# JTAG_Configuration.net
KiCad netlist of a schematic drawn in Altium Designer
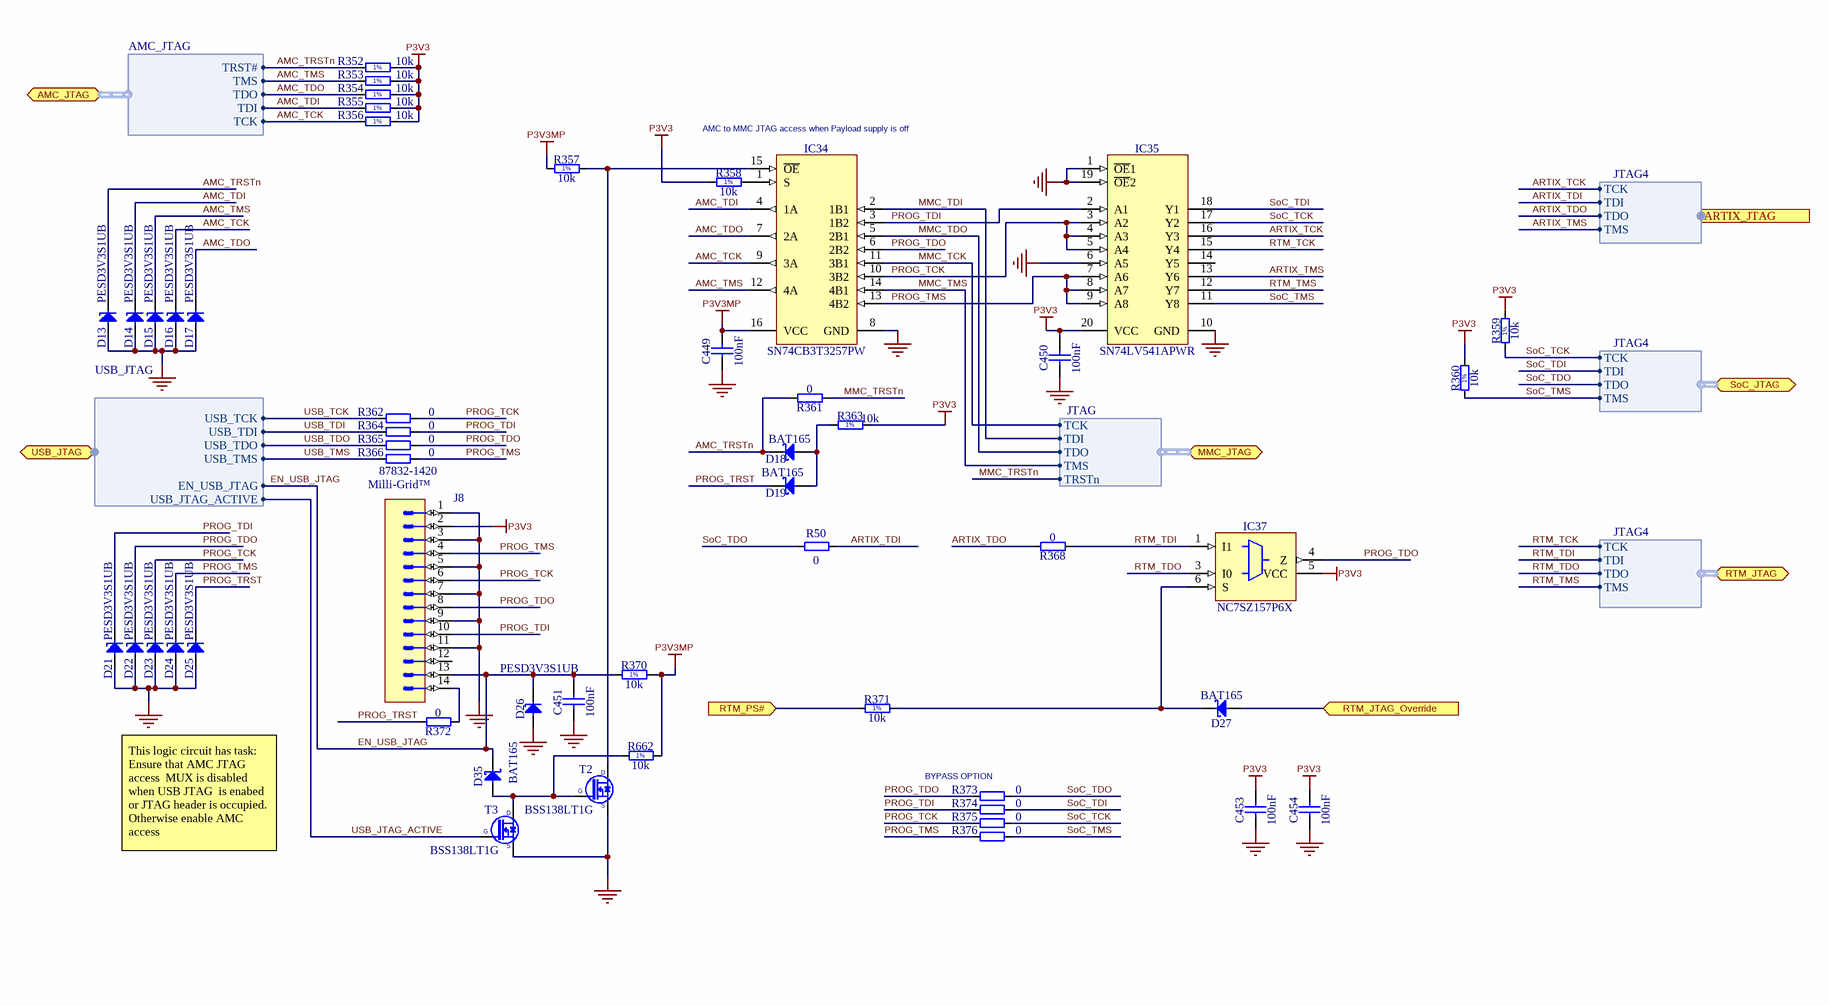
[diagram p0: JTAG_Configuration.SchDoc]

(export (version "E")
  (design (tool "Eeschema 10.0.6"))
  (components
    (comp (ref "C449")
      (value "100nF")
      (footprint "CAPC0603X33N")
      (description "Non-polarised capacitor")
      (fields
        (field (name "MANUFACTURER PART NUMBER") "CC0201_100NF_6.3V_10%_X5R")
        (field (name "MANUFACTURER") "GENERIC")
        (field (name "AUTHOR") "CERN DEM JLC")
      )
      (libsource (lib "Capacitors") (part "Capacitor - non polarized"))
    )
    (comp (ref "C450")
      (value "100nF")
      (footprint "CAPC0603X33N")
      (description "Non-polarised capacitor")
      (fields
        (field (name "MANUFACTURER PART NUMBER") "CC0201_100NF_6.3V_10%_X5R")
        (field (name "MANUFACTURER") "GENERIC")
        (field (name "AUTHOR") "CERN DEM JLC")
      )
      (libsource (lib "Capacitors") (part "Capacitor - non polarized"))
    )
    (comp (ref "C451")
      (value "100nF")
      (footprint "CAPC0603X33N")
      (description "Non-polarised capacitor")
      (fields
        (field (name "MANUFACTURER PART NUMBER") "CC0201_100NF_6.3V_10%_X5R")
        (field (name "MANUFACTURER") "GENERIC")
        (field (name "AUTHOR") "CERN DEM JLC")
      )
      (libsource (lib "Capacitors") (part "Capacitor - non polarized"))
    )
    (comp (ref "C453")
      (value "100nF")
      (footprint "CAPC0603X33N")
      (description "Non-polarised capacitor")
      (fields
        (field (name "MANUFACTURER PART NUMBER") "CC0201_100NF_6.3V_10%_X5R")
        (field (name "MANUFACTURER") "GENERIC")
        (field (name "AUTHOR") "CERN DEM JLC")
      )
      (libsource (lib "Capacitors") (part "Capacitor - non polarized"))
    )
    (comp (ref "C454")
      (value "100nF")
      (footprint "CAPC0603X33N")
      (description "Non-polarised capacitor")
      (fields
        (field (name "MANUFACTURER PART NUMBER") "CC0201_100NF_6.3V_10%_X5R")
        (field (name "MANUFACTURER") "GENERIC")
        (field (name "AUTHOR") "CERN DEM JLC")
      )
      (libsource (lib "Capacitors") (part "Capacitor - non polarized"))
    )
    (comp (ref "D13")
      (value "PESD3V3S1UB")
      (footprint "SODFL1608X65N")
      (description "ESD protection diode")
      (fields
        (field (name "MANUFACTURER") "NXP SEMICONDUCTORS")
        (field (name "VOLTAGE") "3V3")
        (field (name "AUTHOR") "CERN DEM JLC")
      )
      (libsource (lib "ICs And Semiconductors") (part "Diode ESD"))
    )
    (comp (ref "D14")
      (value "PESD3V3S1UB")
      (footprint "SODFL1608X65N")
      (description "ESD protection diode")
      (fields
        (field (name "MANUFACTURER") "NXP SEMICONDUCTORS")
        (field (name "VOLTAGE") "3V3")
        (field (name "AUTHOR") "CERN DEM JLC")
      )
      (libsource (lib "ICs And Semiconductors") (part "Diode ESD"))
    )
    (comp (ref "D15")
      (value "PESD3V3S1UB")
      (footprint "SODFL1608X65N")
      (description "ESD protection diode")
      (fields
        (field (name "MANUFACTURER") "NXP SEMICONDUCTORS")
        (field (name "VOLTAGE") "3V3")
        (field (name "AUTHOR") "CERN DEM JLC")
      )
      (libsource (lib "ICs And Semiconductors") (part "Diode ESD"))
    )
    (comp (ref "D16")
      (value "PESD3V3S1UB")
      (footprint "SODFL1608X65N")
      (description "ESD protection diode")
      (fields
        (field (name "MANUFACTURER") "NXP SEMICONDUCTORS")
        (field (name "VOLTAGE") "3V3")
        (field (name "AUTHOR") "CERN DEM JLC")
      )
      (libsource (lib "ICs And Semiconductors") (part "Diode ESD"))
    )
    (comp (ref "D17")
      (value "PESD3V3S1UB")
      (footprint "SODFL1608X65N")
      (description "ESD protection diode")
      (fields
        (field (name "MANUFACTURER") "NXP SEMICONDUCTORS")
        (field (name "VOLTAGE") "3V3")
        (field (name "AUTHOR") "CERN DEM JLC")
      )
      (libsource (lib "ICs And Semiconductors") (part "Diode ESD"))
    )
    (comp (ref "D18")
      (value "BAT165")
      (footprint "SOD2512X110N")
      (description "Schottky Diode")
      (fields
        (field (name "MANUFACTURER") "INFINEON")
        (field (name "VOLTAGE") "40V")
        (field (name "AUTHOR") "CERN DEM JLC")
      )
      (libsource (lib "ICs And Semiconductors") (part "Diode Schottky"))
    )
    (comp (ref "D19")
      (value "BAT165")
      (footprint "SOD2512X110N")
      (description "Schottky Diode")
      (fields
        (field (name "MANUFACTURER") "INFINEON")
        (field (name "VOLTAGE") "40V")
        (field (name "AUTHOR") "CERN DEM JLC")
      )
      (libsource (lib "ICs And Semiconductors") (part "Diode Schottky"))
    )
    (comp (ref "D21")
      (value "PESD3V3S1UB")
      (footprint "SODFL1608X65N")
      (description "ESD protection diode")
      (fields
        (field (name "MANUFACTURER") "NXP SEMICONDUCTORS")
        (field (name "VOLTAGE") "3V3")
        (field (name "AUTHOR") "CERN DEM JLC")
      )
      (libsource (lib "ICs And Semiconductors") (part "Diode ESD"))
    )
    (comp (ref "D22")
      (value "PESD3V3S1UB")
      (footprint "SODFL1608X65N")
      (description "ESD protection diode")
      (fields
        (field (name "MANUFACTURER") "NXP SEMICONDUCTORS")
        (field (name "VOLTAGE") "3V3")
        (field (name "AUTHOR") "CERN DEM JLC")
      )
      (libsource (lib "ICs And Semiconductors") (part "Diode ESD"))
    )
    (comp (ref "D23")
      (value "PESD3V3S1UB")
      (footprint "SODFL1608X65N")
      (description "ESD protection diode")
      (fields
        (field (name "MANUFACTURER") "NXP SEMICONDUCTORS")
        (field (name "VOLTAGE") "3V3")
        (field (name "AUTHOR") "CERN DEM JLC")
      )
      (libsource (lib "ICs And Semiconductors") (part "Diode ESD"))
    )
    (comp (ref "D24")
      (value "PESD3V3S1UB")
      (footprint "SODFL1608X65N")
      (description "ESD protection diode")
      (fields
        (field (name "MANUFACTURER") "NXP SEMICONDUCTORS")
        (field (name "VOLTAGE") "3V3")
        (field (name "AUTHOR") "CERN DEM JLC")
      )
      (libsource (lib "ICs And Semiconductors") (part "Diode ESD"))
    )
    (comp (ref "D25")
      (value "PESD3V3S1UB")
      (footprint "SODFL1608X65N")
      (description "ESD protection diode")
      (fields
        (field (name "MANUFACTURER") "NXP SEMICONDUCTORS")
        (field (name "VOLTAGE") "3V3")
        (field (name "AUTHOR") "CERN DEM JLC")
      )
      (libsource (lib "ICs And Semiconductors") (part "Diode ESD"))
    )
    (comp (ref "D26")
      (value "PESD3V3S1UB")
      (footprint "SODFL1608X65N")
      (description "ESD protection diode")
      (fields
        (field (name "MANUFACTURER") "NXP SEMICONDUCTORS")
        (field (name "VOLTAGE") "3V3")
        (field (name "AUTHOR") "CERN DEM JLC")
      )
      (libsource (lib "ICs And Semiconductors") (part "Diode ESD"))
    )
    (comp (ref "D27")
      (value "BAT165")
      (footprint "SOD2512X110N")
      (description "Schottky Diode")
      (fields
        (field (name "MANUFACTURER") "INFINEON")
        (field (name "VOLTAGE") "40V")
        (field (name "AUTHOR") "CERN DEM JLC")
      )
      (libsource (lib "ICs And Semiconductors") (part "Diode Schottky"))
    )
    (comp (ref "D35")
      (value "BAT165")
      (footprint "SOD2512X110N")
      (description "Schottky Diode")
      (fields
        (field (name "MANUFACTURER") "INFINEON")
        (field (name "VOLTAGE") "40V")
        (field (name "AUTHOR") "CERN DEM JLC")
      )
      (libsource (lib "ICs And Semiconductors") (part "Diode Schottky"))
    )
    (comp (ref "IC34")
      (value "SN74CB3T3257PW")
      (footprint "SOP65P640X120-16N")
      (description "4-BIT 1-OF-2 FET Multiplexer/Demultiplexer 2.5V/3.3V Low-Voltage Bus Switch 5V Tolerant Shifter")
      (fields (field (name "MANUFACTURER") "TEXAS INSTRUMENTS") (field (name "AUTHOR") "CERN DEM JLC"))
      (libsource (lib "ICs And Semiconductors") (part "743257"))
    )
    (comp (ref "IC35")
      (value "SN74LV541APWR")
      (footprint "SOP65P640X120-20N")
      (description "Octal Buffer/Line Driver with 3-State Outputs")
      (fields (field (name "MANUFACTURER") "TEXAS INSTRUMENTS") (field (name "AUTHOR") "CERN DEM JLC"))
      (libsource (lib "ICs And Semiconductors") (part "74541"))
    )
    (comp (ref "IC37")
      (value "NC7SZ157P6X")
      (footprint "SOT65P210X110-6N")
      (description "TinyLogic® UHS 2-Input Non-Inverting Multiplexer")
      (fields (field (name "MANUFACTURER") "FAIRCHILD SEMICONDUCTOR") (field (name "AUTHOR") "CERN DEM JLC"))
      (libsource (lib "ICs And Semiconductors") (part "NC7SZ157"))
    )
    (comp (ref "J8")
      (value "Milli-Grid™")
      (footprint "MOLEX_87832-1420")
      (description "Connector 14 Male")
      (fields
        (field (name "MANUFACTURER PART NUMBER") "87832-1420")
        (field (name "MANUFACTURER") "MOLEX")
        (field (name "PART NUMBER") "MOLEX_87832-1420")
        (field (name "AUTHOR") "CERN DEM JLC")
      )
      (libsource (lib "Connectors") (part "Connector 14 Male"))
    )
    (comp (ref "R50")
      (value "0")
      (footprint "RESC1005X40N")
      (description "Resistor")
      (fields
        (field (name "MANUFACTURER PART NUMBER") "R0402_0R_JUMPER")
        (field (name "MANUFACTURER") "GENERIC")
        (field (name "AUTHOR") "CERN DEM JLC")
      )
      (libsource (lib "Resistors") (part "Resistor"))
    )
    (comp (ref "R352")
      (value "10k")
      (footprint "RESC1005X40N")
      (description "Resistor - 1%")
      (fields
        (field (name "MANUFACTURER PART NUMBER") "R0402_10K_1%_0.0625W_100PPM")
        (field (name "MANUFACTURER") "GENERIC")
        (field (name "AUTHOR") "CERN DEM JLC")
      )
      (libsource (lib "Resistors") (part "Resistor - 1%"))
    )
    (comp (ref "R353")
      (value "10k")
      (footprint "RESC1005X40N")
      (description "Resistor - 1%")
      (fields
        (field (name "MANUFACTURER PART NUMBER") "R0402_10K_1%_0.0625W_100PPM")
        (field (name "MANUFACTURER") "GENERIC")
        (field (name "AUTHOR") "CERN DEM JLC")
      )
      (libsource (lib "Resistors") (part "Resistor - 1%"))
    )
    (comp (ref "R354")
      (value "10k")
      (footprint "RESC1005X40N")
      (description "Resistor - 1%")
      (fields
        (field (name "MANUFACTURER PART NUMBER") "R0402_10K_1%_0.0625W_100PPM")
        (field (name "MANUFACTURER") "GENERIC")
        (field (name "AUTHOR") "CERN DEM JLC")
      )
      (libsource (lib "Resistors") (part "Resistor - 1%"))
    )
    (comp (ref "R355")
      (value "10k")
      (footprint "RESC1005X40N")
      (description "Resistor - 1%")
      (fields
        (field (name "MANUFACTURER PART NUMBER") "R0402_10K_1%_0.0625W_100PPM")
        (field (name "MANUFACTURER") "GENERIC")
        (field (name "AUTHOR") "CERN DEM JLC")
      )
      (libsource (lib "Resistors") (part "Resistor - 1%"))
    )
    (comp (ref "R356")
      (value "10k")
      (footprint "RESC1005X40N")
      (description "Resistor - 1%")
      (fields
        (field (name "MANUFACTURER PART NUMBER") "R0402_10K_1%_0.0625W_100PPM")
        (field (name "MANUFACTURER") "GENERIC")
        (field (name "AUTHOR") "CERN DEM JLC")
      )
      (libsource (lib "Resistors") (part "Resistor - 1%"))
    )
    (comp (ref "R357")
      (value "10k")
      (footprint "RESC1005X40N")
      (description "Resistor - 1%")
      (fields
        (field (name "MANUFACTURER PART NUMBER") "R0402_10K_1%_0.0625W_100PPM")
        (field (name "MANUFACTURER") "GENERIC")
        (field (name "AUTHOR") "CERN DEM JLC")
      )
      (libsource (lib "Resistors") (part "Resistor - 1%"))
    )
    (comp (ref "R358")
      (value "10k")
      (footprint "RESC1005X40N")
      (description "Resistor - 1%")
      (fields
        (field (name "MANUFACTURER PART NUMBER") "R0402_10K_1%_0.0625W_100PPM")
        (field (name "MANUFACTURER") "GENERIC")
        (field (name "AUTHOR") "CERN DEM JLC")
      )
      (libsource (lib "Resistors") (part "Resistor - 1%"))
    )
    (comp (ref "R359")
      (value "10k")
      (footprint "RESC1005X40N")
      (description "Resistor - 1%")
      (fields
        (field (name "MANUFACTURER PART NUMBER") "R0402_10K_1%_0.0625W_100PPM")
        (field (name "MANUFACTURER") "GENERIC")
        (field (name "AUTHOR") "CERN DEM JLC")
      )
      (libsource (lib "Resistors") (part "Resistor - 1%"))
    )
    (comp (ref "R360")
      (value "10k")
      (footprint "RESC1005X40N")
      (description "Resistor - 1%")
      (fields
        (field (name "MANUFACTURER PART NUMBER") "R0402_10K_1%_0.0625W_100PPM")
        (field (name "MANUFACTURER") "GENERIC")
        (field (name "AUTHOR") "CERN DEM JLC")
      )
      (libsource (lib "Resistors") (part "Resistor - 1%"))
    )
    (comp (ref "R361")
      (value "0")
      (footprint "RESC1005X40N")
      (description "Resistor")
      (fields
        (field (name "MANUFACTURER PART NUMBER") "R0402_0R_JUMPER")
        (field (name "MANUFACTURER") "GENERIC")
        (field (name "AUTHOR") "CERN DEM JLC")
      )
      (libsource (lib "Resistors") (part "Resistor"))
    )
    (comp (ref "R362")
      (value "0")
      (footprint "RESC1005X40N")
      (description "Resistor")
      (fields
        (field (name "MANUFACTURER PART NUMBER") "R0402_0R_JUMPER")
        (field (name "MANUFACTURER") "GENERIC")
        (field (name "AUTHOR") "CERN DEM JLC")
      )
      (libsource (lib "Resistors") (part "Resistor"))
    )
    (comp (ref "R363")
      (value "10k")
      (footprint "RESC1005X40N")
      (description "Resistor - 1%")
      (fields
        (field (name "MANUFACTURER PART NUMBER") "R0402_10K_1%_0.0625W_100PPM")
        (field (name "MANUFACTURER") "GENERIC")
        (field (name "AUTHOR") "CERN DEM JLC")
      )
      (libsource (lib "Resistors") (part "Resistor - 1%"))
    )
    (comp (ref "R364")
      (value "0")
      (footprint "RESC1005X40N")
      (description "Resistor")
      (fields
        (field (name "MANUFACTURER PART NUMBER") "R0402_0R_JUMPER")
        (field (name "MANUFACTURER") "GENERIC")
        (field (name "AUTHOR") "CERN DEM JLC")
      )
      (libsource (lib "Resistors") (part "Resistor"))
    )
    (comp (ref "R365")
      (value "0")
      (footprint "RESC1005X40N")
      (description "Resistor")
      (fields
        (field (name "MANUFACTURER PART NUMBER") "R0402_0R_JUMPER")
        (field (name "MANUFACTURER") "GENERIC")
        (field (name "AUTHOR") "CERN DEM JLC")
      )
      (libsource (lib "Resistors") (part "Resistor"))
    )
    (comp (ref "R366")
      (value "0")
      (footprint "RESC1005X40N")
      (description "Resistor")
      (fields
        (field (name "MANUFACTURER PART NUMBER") "R0402_0R_JUMPER")
        (field (name "MANUFACTURER") "GENERIC")
        (field (name "AUTHOR") "CERN DEM JLC")
      )
      (libsource (lib "Resistors") (part "Resistor"))
    )
    (comp (ref "R368")
      (value "0")
      (footprint "RESC1005X40N")
      (description "Resistor")
      (fields
        (field (name "MANUFACTURER PART NUMBER") "R0402_0R_JUMPER")
        (field (name "MANUFACTURER") "GENERIC")
        (field (name "AUTHOR") "CERN DEM JLC")
      )
      (libsource (lib "Resistors") (part "Resistor"))
    )
    (comp (ref "R370")
      (value "10k")
      (footprint "RESC1005X40N")
      (description "Resistor - 1%")
      (fields
        (field (name "MANUFACTURER PART NUMBER") "R0402_10K_1%_0.0625W_100PPM")
        (field (name "MANUFACTURER") "GENERIC")
        (field (name "AUTHOR") "CERN DEM JLC")
      )
      (libsource (lib "Resistors") (part "Resistor - 1%"))
    )
    (comp (ref "R371")
      (value "10k")
      (footprint "RESC1005X40N")
      (description "Resistor - 1%")
      (fields
        (field (name "MANUFACTURER PART NUMBER") "R0402_10K_1%_0.0625W_100PPM")
        (field (name "MANUFACTURER") "GENERIC")
        (field (name "AUTHOR") "CERN DEM JLC")
      )
      (libsource (lib "Resistors") (part "Resistor - 1%"))
    )
    (comp (ref "R372")
      (value "0")
      (footprint "RESC1005X40N")
      (description "Resistor")
      (fields
        (field (name "MANUFACTURER PART NUMBER") "R0402_0R_JUMPER")
        (field (name "MANUFACTURER") "GENERIC")
        (field (name "AUTHOR") "CERN DEM JLC")
      )
      (libsource (lib "Resistors") (part "Resistor"))
    )
    (comp (ref "R373")
      (value "0")
      (footprint "RESC1005X40N")
      (description "Resistor")
      (fields
        (field (name "MANUFACTURER PART NUMBER") "R0402_0R_JUMPER")
        (field (name "MANUFACTURER") "GENERIC")
        (field (name "AUTHOR") "CERN DEM JLC")
      )
      (libsource (lib "Resistors") (part "Resistor"))
    )
    (comp (ref "R374")
      (value "0")
      (footprint "RESC1005X40N")
      (description "Resistor")
      (fields
        (field (name "MANUFACTURER PART NUMBER") "R0402_0R_JUMPER")
        (field (name "MANUFACTURER") "GENERIC")
        (field (name "AUTHOR") "CERN DEM JLC")
      )
      (libsource (lib "Resistors") (part "Resistor"))
    )
    (comp (ref "R375")
      (value "0")
      (footprint "RESC1005X40N")
      (description "Resistor")
      (fields
        (field (name "MANUFACTURER PART NUMBER") "R0402_0R_JUMPER")
        (field (name "MANUFACTURER") "GENERIC")
        (field (name "AUTHOR") "CERN DEM JLC")
      )
      (libsource (lib "Resistors") (part "Resistor"))
    )
    (comp (ref "R376")
      (value "0")
      (footprint "RESC1005X40N")
      (description "Resistor")
      (fields
        (field (name "MANUFACTURER PART NUMBER") "R0402_0R_JUMPER")
        (field (name "MANUFACTURER") "GENERIC")
        (field (name "AUTHOR") "CERN DEM JLC")
      )
      (libsource (lib "Resistors") (part "Resistor"))
    )
    (comp (ref "R662")
      (value "10k")
      (footprint "RESC1005X40N")
      (description "Resistor - 1%")
      (fields
        (field (name "MANUFACTURER PART NUMBER") "R0402_10K_1%_0.0625W_100PPM")
        (field (name "MANUFACTURER") "GENERIC")
        (field (name "AUTHOR") "CERN DEM JLC")
      )
      (libsource (lib "Resistors") (part "Resistor - 1%"))
    )
    (comp (ref "T2")
      (value "BSS138LT1G")
      (footprint "SOT95P240X110-3N")
      (description "N-CHANNEL MOSFET WITH DIODE")
      (fields (field (name "MANUFACTURER") "ON SEMICONDUCTOR") (field (name "AUTHOR") "CERN DEM JLC"))
      (libsource (lib "ICs And Semiconductors") (part "N-MOSFET-D 1G 2S 3D"))
    )
    (comp (ref "T3")
      (value "BSS138LT1G")
      (footprint "SOT95P240X110-3N")
      (description "N-CHANNEL MOSFET WITH DIODE")
      (fields (field (name "MANUFACTURER") "ON SEMICONDUCTOR") (field (name "AUTHOR") "CERN DEM JLC"))
      (libsource (lib "ICs And Semiconductors") (part "N-MOSFET-D 1G 2S 3D"))
    )
  )
  (nets
    (net (code "5") (name "/AMC_TCK") (class "Default")
      (node (ref "D16") (pin "1") (pinfunction "C_1") (pintype "passive"))
      (node (ref "IC34") (pin "9") (pinfunction "3A_9") (pintype "output"))
      (node (ref "R356") (pin "2") (pinfunction "2_2") (pintype "passive"))
    )
    (net (code "6") (name "/AMC_TDI") (class "Default")
      (node (ref "D14") (pin "1") (pinfunction "C_1") (pintype "passive"))
      (node (ref "IC34") (pin "4") (pinfunction "1A_4") (pintype "output"))
      (node (ref "R355") (pin "2") (pinfunction "2_2") (pintype "passive"))
    )
    (net (code "7") (name "/AMC_TDO") (class "Default")
      (node (ref "D17") (pin "1") (pinfunction "C_1") (pintype "passive"))
      (node (ref "IC34") (pin "7") (pinfunction "2A_7") (pintype "output"))
      (node (ref "R354") (pin "2") (pinfunction "2_2") (pintype "passive"))
    )
    (net (code "8") (name "/AMC_TMS") (class "Default")
      (node (ref "D15") (pin "1") (pinfunction "C_1") (pintype "passive"))
      (node (ref "IC34") (pin "12") (pinfunction "4A_12") (pintype "output"))
      (node (ref "R353") (pin "2") (pinfunction "2_2") (pintype "passive"))
    )
    (net (code "9") (name "/AMC_TRSTn") (class "Default")
      (node (ref "D13") (pin "1") (pinfunction "C_1") (pintype "passive"))
      (node (ref "D18") (pin "1") (pinfunction "C_1") (pintype "passive"))
      (node (ref "R352") (pin "2") (pinfunction "2_2") (pintype "passive"))
      (node (ref "R361") (pin "2") (pinfunction "2_2") (pintype "passive"))
    )
    (net (code "10") (name "/ARTIX_TCK") (class "Default")
      (node (ref "IC35") (pin "16") (pinfunction "Y3_16") (pintype "tri_state"))
    )
    (net (code "11") (name "/ARTIX_TDI") (class "Default")
      (node (ref "R50") (pin "1") (pinfunction "1_1") (pintype "passive"))
    )
    (net (code "12") (name "/ARTIX_TDO") (class "Default")
      (node (ref "R368") (pin "2") (pinfunction "2_2") (pintype "passive"))
    )
    (net (code "13") (name "/ARTIX_TMS") (class "Default")
      (node (ref "IC35") (pin "13") (pinfunction "Y6_13") (pintype "tri_state"))
    )
    (net (code "14") (name "/EN_USB_JTAG") (class "Default")
      (node (ref "C451") (pin "2") (pinfunction "2_2") (pintype "passive"))
      (node (ref "D26") (pin "1") (pinfunction "C_1") (pintype "passive"))
      (node (ref "D35") (pin "1") (pinfunction "C_1") (pintype "passive"))
      (node (ref "J8") (pin "13") (pinfunction "13_13") (pintype "bidirectional"))
      (node (ref "R370") (pin "1") (pinfunction "1_1") (pintype "passive"))
    )
    (net (code "15") (name "/MMC_TCK") (class "Default")
      (node (ref "IC34") (pin "11") (pinfunction "3B1_11") (pintype "input"))
    )
    (net (code "16") (name "/MMC_TDI") (class "Default")
      (node (ref "IC34") (pin "2") (pinfunction "1B1_2") (pintype "input"))
    )
    (net (code "17") (name "/MMC_TDO") (class "Default")
      (node (ref "IC34") (pin "5") (pinfunction "2B1_5") (pintype "input"))
    )
    (net (code "18") (name "/MMC_TMS") (class "Default")
      (node (ref "IC34") (pin "14") (pinfunction "4B1_14") (pintype "input"))
    )
    (net (code "19") (name "/MMC_TRSTn") (class "Default")
      (node (ref "R361") (pin "1") (pinfunction "1_1") (pintype "passive"))
    )
    (net (code "20") (name "/PROG_TCK") (class "Default")
      (node (ref "D23") (pin "1") (pinfunction "C_1") (pintype "passive"))
      (node (ref "IC34") (pin "10") (pinfunction "3B2_10") (pintype "input"))
      (node (ref "IC35") (pin "3") (pinfunction "A2_3") (pintype "input"))
      (node (ref "IC35") (pin "4") (pinfunction "A3_4") (pintype "input"))
      (node (ref "IC35") (pin "5") (pinfunction "A4_5") (pintype "input"))
      (node (ref "J8") (pin "6") (pinfunction "6_6") (pintype "bidirectional"))
      (node (ref "R362") (pin "1") (pinfunction "1_1") (pintype "passive"))
      (node (ref "R375") (pin "2") (pinfunction "2_2") (pintype "passive"))
    )
    (net (code "21") (name "/PROG_TDI") (class "Default")
      (node (ref "D21") (pin "1") (pinfunction "C_1") (pintype "passive"))
      (node (ref "IC34") (pin "3") (pinfunction "1B2_3") (pintype "input"))
      (node (ref "IC35") (pin "2") (pinfunction "A1_2") (pintype "input"))
      (node (ref "J8") (pin "10") (pinfunction "10_10") (pintype "bidirectional"))
      (node (ref "R364") (pin "1") (pinfunction "1_1") (pintype "passive"))
      (node (ref "R374") (pin "2") (pinfunction "2_2") (pintype "passive"))
    )
    (net (code "22") (name "/PROG_TDO") (class "Default")
      (node (ref "D22") (pin "1") (pinfunction "C_1") (pintype "passive"))
      (node (ref "IC34") (pin "6") (pinfunction "2B2_6") (pintype "input"))
      (node (ref "IC37") (pin "4") (pinfunction "Z_4") (pintype "output"))
      (node (ref "J8") (pin "8") (pinfunction "8_8") (pintype "bidirectional"))
      (node (ref "R365") (pin "1") (pinfunction "1_1") (pintype "passive"))
      (node (ref "R373") (pin "2") (pinfunction "2_2") (pintype "passive"))
    )
    (net (code "23") (name "/PROG_TMS") (class "Default")
      (node (ref "D24") (pin "1") (pinfunction "C_1") (pintype "passive"))
      (node (ref "IC34") (pin "13") (pinfunction "4B2_13") (pintype "input"))
      (node (ref "IC35") (pin "7") (pinfunction "A6_7") (pintype "input"))
      (node (ref "IC35") (pin "8") (pinfunction "A7_8") (pintype "input"))
      (node (ref "IC35") (pin "9") (pinfunction "A8_9") (pintype "input"))
      (node (ref "J8") (pin "4") (pinfunction "4_4") (pintype "bidirectional"))
      (node (ref "R366") (pin "1") (pinfunction "1_1") (pintype "passive"))
      (node (ref "R376") (pin "2") (pinfunction "2_2") (pintype "passive"))
    )
    (net (code "24") (name "/PROG_TRST") (class "Default")
      (node (ref "D19") (pin "1") (pinfunction "C_1") (pintype "passive"))
      (node (ref "D25") (pin "1") (pinfunction "C_1") (pintype "passive"))
      (node (ref "R372") (pin "2") (pinfunction "2_2") (pintype "passive"))
    )
    (net (code "25") (name "/RTM_JTAG_Override") (class "Default")
      (node (ref "D27") (pin "2") (pinfunction "A_2") (pintype "passive"))
    )
    (net (code "26") (name "/RTM_PS#") (class "Default")
      (node (ref "R371") (pin "2") (pinfunction "2_2") (pintype "passive"))
    )
    (net (code "27") (name "/RTM_TCK") (class "Default")
      (node (ref "IC35") (pin "15") (pinfunction "Y4_15") (pintype "tri_state"))
    )
    (net (code "28") (name "/RTM_TDI") (class "Default")
      (node (ref "IC37") (pin "1") (pinfunction "I1_1") (pintype "input"))
      (node (ref "R368") (pin "1") (pinfunction "1_1") (pintype "passive"))
    )
    (net (code "29") (name "/RTM_TDO") (class "Default")
      (node (ref "IC37") (pin "3") (pinfunction "I0_3") (pintype "input"))
    )
    (net (code "30") (name "/RTM_TMS") (class "Default")
      (node (ref "IC35") (pin "12") (pinfunction "Y7_12") (pintype "tri_state"))
    )
    (net (code "31") (name "/SoC_TCK") (class "Default")
      (node (ref "IC35") (pin "17") (pinfunction "Y2_17") (pintype "tri_state"))
      (node (ref "R359") (pin "1") (pinfunction "1_1") (pintype "passive"))
      (node (ref "R375") (pin "1") (pinfunction "1_1") (pintype "passive"))
    )
    (net (code "32") (name "/SoC_TDI") (class "Default")
      (node (ref "IC35") (pin "18") (pinfunction "Y1_18") (pintype "tri_state"))
      (node (ref "R374") (pin "1") (pinfunction "1_1") (pintype "passive"))
    )
    (net (code "33") (name "/SoC_TDO") (class "Default")
      (node (ref "R373") (pin "1") (pinfunction "1_1") (pintype "passive"))
      (node (ref "R50") (pin "2") (pinfunction "2_2") (pintype "passive"))
    )
    (net (code "34") (name "/SoC_TMS") (class "Default")
      (node (ref "IC35") (pin "11") (pinfunction "Y8_11") (pintype "tri_state"))
      (node (ref "R360") (pin "1") (pinfunction "1_1") (pintype "passive"))
      (node (ref "R376") (pin "1") (pinfunction "1_1") (pintype "passive"))
    )
    (net (code "35") (name "/USB_JTAG_ACTIVE") (class "Default")
      (node (ref "T3") (pin "1") (pinfunction "G_1") (pintype "passive"))
    )
    (net (code "36") (name "/USB_TCK") (class "Default")
      (node (ref "R362") (pin "2") (pinfunction "2_2") (pintype "passive"))
    )
    (net (code "37") (name "/USB_TDI") (class "Default")
      (node (ref "R364") (pin "2") (pinfunction "2_2") (pintype "passive"))
    )
    (net (code "38") (name "/USB_TDO") (class "Default")
      (node (ref "R365") (pin "2") (pinfunction "2_2") (pintype "passive"))
    )
    (net (code "39") (name "/USB_TMS") (class "Default")
      (node (ref "R366") (pin "2") (pinfunction "2_2") (pintype "passive"))
    )
    (net (code "44") (name "GND") (class "Default")
      (node (ref "C449") (pin "1") (pinfunction "1_1") (pintype "passive"))
      (node (ref "C450") (pin "1") (pinfunction "1_1") (pintype "passive"))
      (node (ref "C451") (pin "1") (pinfunction "1_1") (pintype "passive"))
      (node (ref "C453") (pin "1") (pinfunction "1_1") (pintype "passive"))
      (node (ref "C454") (pin "1") (pinfunction "1_1") (pintype "passive"))
      (node (ref "D13") (pin "2") (pinfunction "A_2") (pintype "passive"))
      (node (ref "D14") (pin "2") (pinfunction "A_2") (pintype "passive"))
      (node (ref "D15") (pin "2") (pinfunction "A_2") (pintype "passive"))
      (node (ref "D16") (pin "2") (pinfunction "A_2") (pintype "passive"))
      (node (ref "D17") (pin "2") (pinfunction "A_2") (pintype "passive"))
      (node (ref "D21") (pin "2") (pinfunction "A_2") (pintype "passive"))
      (node (ref "D22") (pin "2") (pinfunction "A_2") (pintype "passive"))
      (node (ref "D23") (pin "2") (pinfunction "A_2") (pintype "passive"))
      (node (ref "D24") (pin "2") (pinfunction "A_2") (pintype "passive"))
      (node (ref "D25") (pin "2") (pinfunction "A_2") (pintype "passive"))
      (node (ref "D26") (pin "2") (pinfunction "A_2") (pintype "passive"))
      (node (ref "IC34") (pin "8") (pinfunction "GND_8") (pintype "power_in"))
      (node (ref "IC35") (pin "1") (pinfunction "~{OE}1_1") (pintype "input"))
      (node (ref "IC35") (pin "10") (pinfunction "GND_10") (pintype "power_in"))
      (node (ref "IC35") (pin "19") (pinfunction "~{OE}2_19") (pintype "input"))
      (node (ref "IC35") (pin "6") (pinfunction "A5_6") (pintype "input"))
      (node (ref "IC37") (pin "2") (pinfunction "GND_2") (pintype "power_in"))
      (node (ref "J8") (pin "1") (pinfunction "1_1") (pintype "bidirectional"))
      (node (ref "J8") (pin "11") (pinfunction "11_11") (pintype "bidirectional"))
      (node (ref "J8") (pin "3") (pinfunction "3_3") (pintype "bidirectional"))
      (node (ref "J8") (pin "5") (pinfunction "5_5") (pintype "bidirectional"))
      (node (ref "J8") (pin "7") (pinfunction "7_7") (pintype "bidirectional"))
      (node (ref "J8") (pin "9") (pinfunction "9_9") (pintype "bidirectional"))
      (node (ref "T2") (pin "2") (pinfunction "S_2") (pintype "passive"))
      (node (ref "T3") (pin "2") (pinfunction "S_2") (pintype "passive"))
    )
    (net (code "45") (name "Net-(D18-A)") (class "Default")
      (node (ref "D18") (pin "2") (pinfunction "A_2") (pintype "passive"))
      (node (ref "D19") (pin "2") (pinfunction "A_2") (pintype "passive"))
      (node (ref "R363") (pin "2") (pinfunction "2_2") (pintype "passive"))
    )
    (net (code "46") (name "Net-(D27-C)") (class "Default")
      (node (ref "D27") (pin "1") (pinfunction "C_1") (pintype "passive"))
      (node (ref "IC37") (pin "6") (pinfunction "S_6") (pintype "input"))
      (node (ref "R371") (pin "1") (pinfunction "1_1") (pintype "passive"))
    )
    (net (code "47") (name "Net-(D35-A)") (class "Default")
      (node (ref "D35") (pin "2") (pinfunction "A_2") (pintype "passive"))
      (node (ref "R662") (pin "1") (pinfunction "1_1") (pintype "passive"))
      (node (ref "T2") (pin "1") (pinfunction "G_1") (pintype "passive"))
      (node (ref "T3") (pin "3") (pinfunction "D_3") (pintype "passive"))
    )
    (net (code "48") (name "Net-(IC34-S)") (class "Default")
      (node (ref "IC34") (pin "1") (pinfunction "S_1") (pintype "input"))
      (node (ref "R358") (pin "1") (pinfunction "1_1") (pintype "passive"))
    )
    (net (code "49") (name "Net-(IC34-~{OE})") (class "Default")
      (node (ref "IC34") (pin "15") (pinfunction "~{OE}_15") (pintype "input"))
      (node (ref "R357") (pin "1") (pinfunction "1_1") (pintype "passive"))
      (node (ref "T2") (pin "3") (pinfunction "D_3") (pintype "passive"))
    )
    (net (code "50") (name "Net-(J8-Pad14)") (class "Default")
      (node (ref "J8") (pin "14") (pinfunction "14_14") (pintype "bidirectional"))
      (node (ref "R372") (pin "1") (pinfunction "1_1") (pintype "passive"))
    )
    (net (code "51") (name "P3V3") (class "Default")
      (node (ref "C450") (pin "2") (pinfunction "2_2") (pintype "passive"))
      (node (ref "C453") (pin "2") (pinfunction "2_2") (pintype "passive"))
      (node (ref "C454") (pin "2") (pinfunction "2_2") (pintype "passive"))
      (node (ref "IC35") (pin "20") (pinfunction "VCC_20") (pintype "power_in"))
      (node (ref "IC37") (pin "5") (pinfunction "VCC_5") (pintype "power_in"))
      (node (ref "J8") (pin "2") (pinfunction "2_2") (pintype "bidirectional"))
      (node (ref "R352") (pin "1") (pinfunction "1_1") (pintype "passive"))
      (node (ref "R353") (pin "1") (pinfunction "1_1") (pintype "passive"))
      (node (ref "R354") (pin "1") (pinfunction "1_1") (pintype "passive"))
      (node (ref "R355") (pin "1") (pinfunction "1_1") (pintype "passive"))
      (node (ref "R356") (pin "1") (pinfunction "1_1") (pintype "passive"))
      (node (ref "R358") (pin "2") (pinfunction "2_2") (pintype "passive"))
      (node (ref "R359") (pin "2") (pinfunction "2_2") (pintype "passive"))
      (node (ref "R360") (pin "2") (pinfunction "2_2") (pintype "passive"))
      (node (ref "R363") (pin "1") (pinfunction "1_1") (pintype "passive"))
    )
    (net (code "52") (name "P3V3MP") (class "Default")
      (node (ref "C449") (pin "2") (pinfunction "2_2") (pintype "passive"))
      (node (ref "IC34") (pin "16") (pinfunction "VCC_16") (pintype "power_in"))
      (node (ref "R357") (pin "2") (pinfunction "2_2") (pintype "passive"))
      (node (ref "R370") (pin "2") (pinfunction "2_2") (pintype "passive"))
      (node (ref "R662") (pin "2") (pinfunction "2_2") (pintype "passive"))
    )
    (net (code "53") (name "unconnected-(IC35-Y5-Pad14)") (class "Default")
      (node (ref "IC35") (pin "14") (pinfunction "Y5_14") (pintype "tri_state"))
    )
    (net (code "54") (name "unconnected-(J8-Pad12)") (class "Default")
      (node (ref "J8") (pin "12") (pinfunction "12_12") (pintype "bidirectional"))
    )
  )
)
